# MCU.net
KiCad netlist of a schematic drawn in Altium Designer
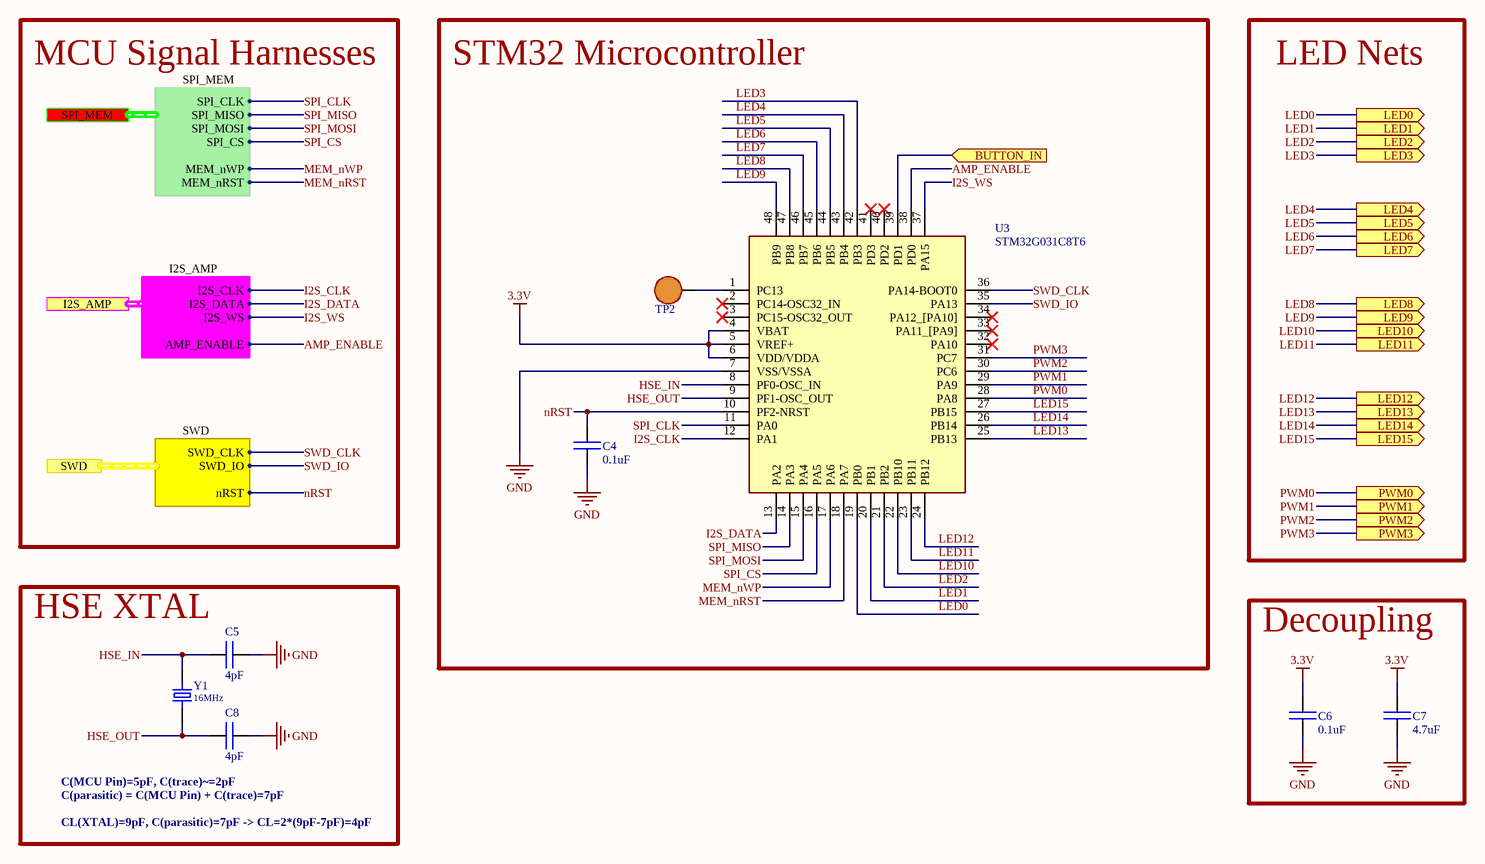
[diagram p0: MCU.SchDoc]

(export (version "E")
  (design (tool "Eeschema 10.0.6"))
  (components
    (comp (ref "C4")
      (value "0.1uF")
      (footprint "Christmas-2024_TSO-PCB:0402C")
      (description "Capacitor")
      (fields (field (name "MFR") "Samsung") (field (name "Comment") "CAP"))
      (libsource (lib "Christmas-2024_TSO-PCB") (part "CAP"))
    )
    (comp (ref "C5")
      (value "4pF")
      (footprint "Christmas-2024_TSO-PCB:0402C")
      (description "Capacitor")
      (fields (field (name "MFR") "Murata") (field (name "Comment") "CAP"))
      (libsource (lib "Christmas-2024_TSO-PCB") (part "CAP"))
    )
    (comp (ref "C6")
      (value "0.1uF")
      (footprint "Christmas-2024_TSO-PCB:0402C")
      (description "Capacitor")
      (fields (field (name "MFR") "Samsung") (field (name "Comment") "CAP"))
      (libsource (lib "Christmas-2024_TSO-PCB") (part "CAP"))
    )
    (comp (ref "C7")
      (value "4.7uF")
      (footprint "Christmas-2024_TSO-PCB:0402C")
      (description "Capacitor")
      (fields (field (name "MFR") "Samsung") (field (name "Comment") "CAP"))
      (libsource (lib "Christmas-2024_TSO-PCB") (part "CAP"))
    )
    (comp (ref "C8")
      (value "4pF")
      (footprint "Christmas-2024_TSO-PCB:0402C")
      (description "Capacitor")
      (fields (field (name "MFR") "Murata") (field (name "Comment") "CAP"))
      (libsource (lib "Christmas-2024_TSO-PCB") (part "CAP"))
    )
    (comp (ref "TP2")
      (value "RCWCTE")
      (footprint "Christmas-2024_TSO-PCB:RCWCTE")
      (description "Test Point, Surface Mount")
      (fields (field (name "MFR") "KOA Speer Electronics, Inc."))
      (libsource (lib "Christmas-2024_TSO-PCB") (part "TEST POINT"))
    )
    (comp (ref "U3")
      (value "STM32G031C8T6")
      (footprint "Christmas-2024_TSO-PCB:48-LQFP")
      (fields (field (name "MFR") "STMicroelectronics"))
      (libsource (lib "Christmas-2024_TSO-PCB") (part "STM32G031C6T6"))
    )
    (comp (ref "Y1")
      (value "16MHz")
      (footprint "Christmas-2024_TSO-PCB:4-SMD_NL")
      (description "CRYSTAL 16.0000MHZ 9PF SMD")
      (fields (field (name "MFR") "EPSON"))
      (libsource (lib "Christmas-2024_TSO-PCB") (part "16 MHz XTAL"))
    )
  )
  (nets
    (net (code "4") (name "/AMP_ENABLE") (class "Default")
      (node (ref "U3") (pin "38") (pinfunction "PD0_38") (pintype "passive"))
    )
    (net (code "5") (name "/BUTTON_IN") (class "Default")
      (node (ref "U3") (pin "39") (pinfunction "PD1_39") (pintype "passive"))
    )
    (net (code "6") (name "/HSE_IN") (class "Default")
      (node (ref "C5") (pin "2") (pinfunction "2_2") (pintype "passive"))
      (node (ref "U3") (pin "8") (pinfunction "PF0-OSC_IN_8") (pintype "passive"))
      (node (ref "Y1") (pin "2") (pinfunction "2_2") (pintype "passive"))
    )
    (net (code "7") (name "/HSE_OUT") (class "Default")
      (node (ref "C8") (pin "2") (pinfunction "2_2") (pintype "passive"))
      (node (ref "U3") (pin "9") (pinfunction "PF1-OSC_OUT_9") (pintype "passive"))
      (node (ref "Y1") (pin "1") (pinfunction "1_1") (pintype "passive"))
    )
    (net (code "8") (name "/I2S_CLK") (class "Default")
      (node (ref "U3") (pin "12") (pinfunction "PA1_12") (pintype "passive"))
    )
    (net (code "9") (name "/I2S_DATA") (class "Default")
      (node (ref "U3") (pin "13") (pinfunction "PA2_13") (pintype "passive"))
    )
    (net (code "10") (name "/I2S_WS") (class "Default")
      (node (ref "U3") (pin "37") (pinfunction "PA15_37") (pintype "passive"))
    )
    (net (code "11") (name "/LED0") (class "Default")
      (node (ref "U3") (pin "19") (pinfunction "PB0_19") (pintype "passive"))
    )
    (net (code "12") (name "/LED1") (class "Default")
      (node (ref "U3") (pin "20") (pinfunction "PB1_20") (pintype "passive"))
    )
    (net (code "13") (name "/LED2") (class "Default")
      (node (ref "U3") (pin "21") (pinfunction "PB2_21") (pintype "passive"))
    )
    (net (code "14") (name "/LED3") (class "Default")
      (node (ref "U3") (pin "42") (pinfunction "PB3_42") (pintype "passive"))
    )
    (net (code "15") (name "/LED4") (class "Default")
      (node (ref "U3") (pin "43") (pinfunction "PB4_43") (pintype "passive"))
    )
    (net (code "16") (name "/LED5") (class "Default")
      (node (ref "U3") (pin "44") (pinfunction "PB5_44") (pintype "passive"))
    )
    (net (code "17") (name "/LED6") (class "Default")
      (node (ref "U3") (pin "45") (pinfunction "PB6_45") (pintype "passive"))
    )
    (net (code "18") (name "/LED7") (class "Default")
      (node (ref "U3") (pin "46") (pinfunction "PB7_46") (pintype "passive"))
    )
    (net (code "19") (name "/LED8") (class "Default")
      (node (ref "U3") (pin "47") (pinfunction "PB8_47") (pintype "passive"))
    )
    (net (code "20") (name "/LED9") (class "Default")
      (node (ref "U3") (pin "48") (pinfunction "PB9_48") (pintype "passive"))
    )
    (net (code "21") (name "/LED10") (class "Default")
      (node (ref "U3") (pin "22") (pinfunction "PB10_22") (pintype "passive"))
    )
    (net (code "22") (name "/LED11") (class "Default")
      (node (ref "U3") (pin "23") (pinfunction "PB11_23") (pintype "passive"))
    )
    (net (code "23") (name "/LED12") (class "Default")
      (node (ref "U3") (pin "24") (pinfunction "PB12_24") (pintype "passive"))
    )
    (net (code "24") (name "/LED13") (class "Default")
      (node (ref "U3") (pin "25") (pinfunction "PB13_25") (pintype "passive"))
    )
    (net (code "25") (name "/LED14") (class "Default")
      (node (ref "U3") (pin "26") (pinfunction "PB14_26") (pintype "passive"))
    )
    (net (code "26") (name "/LED15") (class "Default")
      (node (ref "U3") (pin "27") (pinfunction "PB15_27") (pintype "passive"))
    )
    (net (code "27") (name "/MEM_nRST") (class "Default")
      (node (ref "U3") (pin "18") (pinfunction "PA7_18") (pintype "passive"))
    )
    (net (code "28") (name "/MEM_nWP") (class "Default")
      (node (ref "U3") (pin "17") (pinfunction "PA6_17") (pintype "passive"))
    )
    (net (code "29") (name "/PWM0") (class "Default")
      (node (ref "U3") (pin "28") (pinfunction "PA8_28") (pintype "passive"))
    )
    (net (code "30") (name "/PWM1") (class "Default")
      (node (ref "U3") (pin "29") (pinfunction "PA9_29") (pintype "passive"))
    )
    (net (code "31") (name "/PWM2") (class "Default")
      (node (ref "U3") (pin "30") (pinfunction "PC6_30") (pintype "passive"))
    )
    (net (code "32") (name "/PWM3") (class "Default")
      (node (ref "U3") (pin "31") (pinfunction "PC7_31") (pintype "passive"))
    )
    (net (code "33") (name "/SPI_CLK") (class "Default")
      (node (ref "U3") (pin "11") (pinfunction "PA0_11") (pintype "passive"))
    )
    (net (code "34") (name "/SPI_CS") (class "Default")
      (node (ref "U3") (pin "16") (pinfunction "PA5_16") (pintype "passive"))
    )
    (net (code "35") (name "/SPI_MISO") (class "Default")
      (node (ref "U3") (pin "14") (pinfunction "PA3_14") (pintype "passive"))
    )
    (net (code "36") (name "/SPI_MOSI") (class "Default")
      (node (ref "U3") (pin "15") (pinfunction "PA4_15") (pintype "passive"))
    )
    (net (code "37") (name "/SWD_CLK") (class "Default")
      (node (ref "U3") (pin "36") (pinfunction "PA14-BOOT0_36") (pintype "passive"))
    )
    (net (code "38") (name "/SWD_IO") (class "Default")
      (node (ref "U3") (pin "35") (pinfunction "PA13_35") (pintype "passive"))
    )
    (net (code "39") (name "/nRST") (class "Default")
      (node (ref "C4") (pin "2") (pinfunction "2_2") (pintype "passive"))
      (node (ref "U3") (pin "10") (pinfunction "PF2-NRST_10") (pintype "passive"))
    )
    (net (code "43") (name "3.3V") (class "Default")
      (node (ref "C6") (pin "2") (pinfunction "2_2") (pintype "passive"))
      (node (ref "C7") (pin "2") (pinfunction "2_2") (pintype "passive"))
      (node (ref "U3") (pin "4") (pinfunction "VBAT_4") (pintype "passive"))
      (node (ref "U3") (pin "5") (pinfunction "VREF+_5") (pintype "passive"))
      (node (ref "U3") (pin "6") (pinfunction "VDD/VDDA_6") (pintype "passive"))
    )
    (net (code "44") (name "GND") (class "Default")
      (node (ref "C4") (pin "1") (pinfunction "1_1") (pintype "passive"))
      (node (ref "C5") (pin "1") (pinfunction "1_1") (pintype "passive"))
      (node (ref "C6") (pin "1") (pinfunction "1_1") (pintype "passive"))
      (node (ref "C7") (pin "1") (pinfunction "1_1") (pintype "passive"))
      (node (ref "C8") (pin "1") (pinfunction "1_1") (pintype "passive"))
      (node (ref "U3") (pin "7") (pinfunction "VSS/VSSA_7") (pintype "passive"))
    )
    (net (code "45") (name "Net-(TP2-0)") (class "Default")
      (node (ref "TP2") (pin "1") (pinfunction "0_1") (pintype "passive"))
      (node (ref "U3") (pin "1") (pinfunction "PC13_1") (pintype "passive"))
    )
    (net (code "46") (name "unconnected-(U3-PA10-Pad32)") (class "Default")
      (node (ref "U3") (pin "32") (pinfunction "PA10_32") (pintype "passive+no_connect"))
    )
    (net (code "47") (name "unconnected-(U3-PA11_[PA9]-Pad33)") (class "Default")
      (node (ref "U3") (pin "33") (pinfunction "PA11_[PA9]_33") (pintype "passive+no_connect"))
    )
    (net (code "48") (name "unconnected-(U3-PA12_[PA10]-Pad34)") (class "Default")
      (node (ref "U3") (pin "34") (pinfunction "PA12_[PA10]_34") (pintype "passive+no_connect"))
    )
    (net (code "49") (name "unconnected-(U3-PC14-OSC32_IN-Pad2)") (class "Default")
      (node (ref "U3") (pin "2") (pinfunction "PC14-OSC32_IN_2") (pintype "passive+no_connect"))
    )
    (net (code "50") (name "unconnected-(U3-PC15-OSC32_OUT-Pad3)") (class "Default")
      (node (ref "U3") (pin "3") (pinfunction "PC15-OSC32_OUT_3") (pintype "passive+no_connect"))
    )
    (net (code "51") (name "unconnected-(U3-PD2-Pad40)") (class "Default")
      (node (ref "U3") (pin "40") (pinfunction "PD2_40") (pintype "passive+no_connect"))
    )
    (net (code "52") (name "unconnected-(U3-PD3-Pad41)") (class "Default")
      (node (ref "U3") (pin "41") (pinfunction "PD3_41") (pintype "passive+no_connect"))
    )
  )
)
